# Channel.net
KiCad netlist of a schematic drawn in Altium Designer
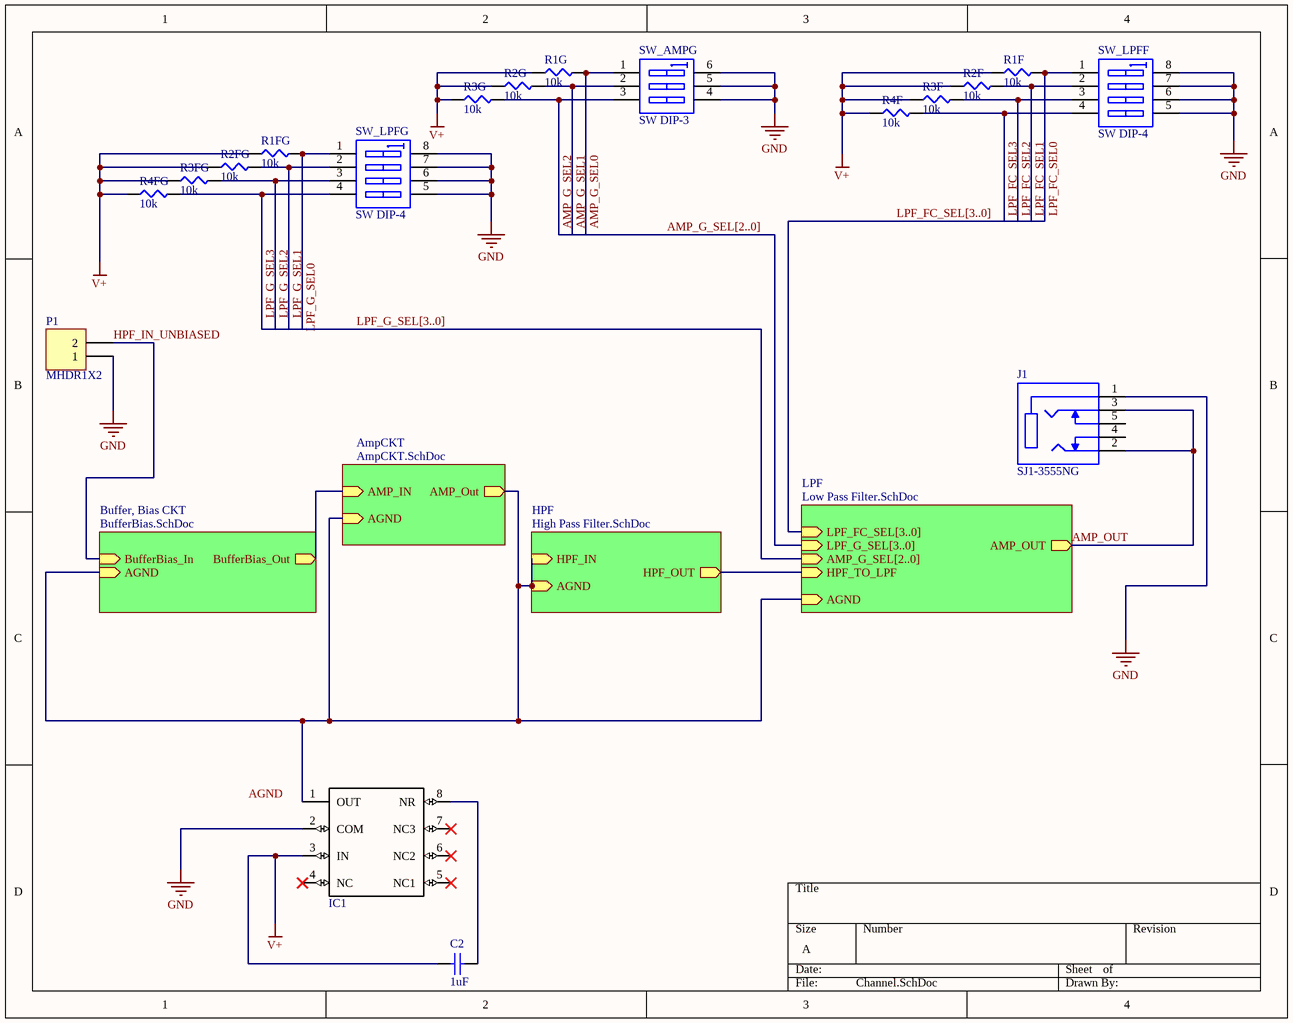
[diagram p0: Channel.SchDoc]

(export (version "E")
  (design (tool "Eeschema 10.0.6"))
  (components
    (comp (ref "C2")
      (value "1uF")
      (footprint "SMD-0805C")
      (description "Unpolarized Capacitor")
      (fields (field (name "Comment") "Cap"))
      (libsource (lib "URC_Lib") (part "Cap"))
    )
    (comp (ref "IC1")
      (value "TLE2426")
      (footprint "SO8_M")
      (fields (field (name "MF") "Texas Instruments"))
      (libsource (lib "TLE2426") (part "TLE2426"))
    )
    (comp (ref "J1")
      (value "SJ1-3555NG")
      (footprint "CUI_SJ1-3555NG")
      (description "3.5 mm, Stereo, Right Angle, Through Hole, Isolated Ground, Kinked Pins, Audio Jack Connector")
      (fields (field (name "MF") "CUI Devices"))
      (libsource (lib "SnapEDAsch") (part "SJ1-3555NG"))
    )
    (comp (ref "P1")
      (value "MHDR1X2")
      (footprint "MHDR1X2")
      (description "Header, 2-Pin")
      (fields (field (name "PUBLISHER") "Altium Limited"))
      (libsource (lib "Miscellaneous Connectors") (part "MHDR1X2"))
    )
    (comp (ref "R1F")
      (value "10k")
      (footprint "SMD-0805-RES")
      (description "RES SMD 10K OHM 1% 1/8W 0805")
      (fields
        (field (name "PART NUMBER") "ERJ-6ENF1002V")
        (field (name "DIGI-KEY PART NUMBER") "P10.0KCCT-ND")
      )
      (libsource (lib "Panasonic_ERJ_0805") (part "ERJ-6ENF1002V"))
    )
    (comp (ref "R1FG")
      (value "10k")
      (footprint "SMD-0805-RES")
      (description "RES SMD 10K OHM 1% 1/8W 0805")
      (fields
        (field (name "PART NUMBER") "ERJ-6ENF1002V")
        (field (name "DIGI-KEY PART NUMBER") "P10.0KCCT-ND")
      )
      (libsource (lib "Panasonic_ERJ_0805") (part "ERJ-6ENF1002V"))
    )
    (comp (ref "R1G")
      (value "10k")
      (footprint "SMD-0805-RES")
      (description "RES SMD 10K OHM 1% 1/8W 0805")
      (fields
        (field (name "PART NUMBER") "ERJ-6ENF1002V")
        (field (name "DIGI-KEY PART NUMBER") "P10.0KCCT-ND")
      )
      (libsource (lib "Panasonic_ERJ_0805") (part "ERJ-6ENF1002V"))
    )
    (comp (ref "R2F")
      (value "10k")
      (footprint "SMD-0805-RES")
      (description "RES SMD 10K OHM 1% 1/8W 0805")
      (fields
        (field (name "PART NUMBER") "ERJ-6ENF1002V")
        (field (name "DIGI-KEY PART NUMBER") "P10.0KCCT-ND")
      )
      (libsource (lib "Panasonic_ERJ_0805") (part "ERJ-6ENF1002V"))
    )
    (comp (ref "R2FG")
      (value "10k")
      (footprint "SMD-0805-RES")
      (description "RES SMD 10K OHM 1% 1/8W 0805")
      (fields
        (field (name "PART NUMBER") "ERJ-6ENF1002V")
        (field (name "DIGI-KEY PART NUMBER") "P10.0KCCT-ND")
      )
      (libsource (lib "Panasonic_ERJ_0805") (part "ERJ-6ENF1002V"))
    )
    (comp (ref "R2G")
      (value "10k")
      (footprint "SMD-0805-RES")
      (description "RES SMD 10K OHM 1% 1/8W 0805")
      (fields
        (field (name "PART NUMBER") "ERJ-6ENF1002V")
        (field (name "DIGI-KEY PART NUMBER") "P10.0KCCT-ND")
      )
      (libsource (lib "Panasonic_ERJ_0805") (part "ERJ-6ENF1002V"))
    )
    (comp (ref "R3F")
      (value "10k")
      (footprint "SMD-0805-RES")
      (description "RES SMD 10K OHM 1% 1/8W 0805")
      (fields
        (field (name "PART NUMBER") "ERJ-6ENF1002V")
        (field (name "DIGI-KEY PART NUMBER") "P10.0KCCT-ND")
      )
      (libsource (lib "Panasonic_ERJ_0805") (part "ERJ-6ENF1002V"))
    )
    (comp (ref "R3FG")
      (value "10k")
      (footprint "SMD-0805-RES")
      (description "RES SMD 10K OHM 1% 1/8W 0805")
      (fields
        (field (name "PART NUMBER") "ERJ-6ENF1002V")
        (field (name "DIGI-KEY PART NUMBER") "P10.0KCCT-ND")
      )
      (libsource (lib "Panasonic_ERJ_0805") (part "ERJ-6ENF1002V"))
    )
    (comp (ref "R3G")
      (value "10k")
      (footprint "SMD-0805-RES")
      (description "RES SMD 10K OHM 1% 1/8W 0805")
      (fields
        (field (name "PART NUMBER") "ERJ-6ENF1002V")
        (field (name "DIGI-KEY PART NUMBER") "P10.0KCCT-ND")
      )
      (libsource (lib "Panasonic_ERJ_0805") (part "ERJ-6ENF1002V"))
    )
    (comp (ref "R4F")
      (value "10k")
      (footprint "SMD-0805-RES")
      (description "RES SMD 10K OHM 1% 1/8W 0805")
      (fields
        (field (name "PART NUMBER") "ERJ-6ENF1002V")
        (field (name "DIGI-KEY PART NUMBER") "P10.0KCCT-ND")
      )
      (libsource (lib "Panasonic_ERJ_0805") (part "ERJ-6ENF1002V"))
    )
    (comp (ref "R4FG")
      (value "10k")
      (footprint "SMD-0805-RES")
      (description "RES SMD 10K OHM 1% 1/8W 0805")
      (fields
        (field (name "PART NUMBER") "ERJ-6ENF1002V")
        (field (name "DIGI-KEY PART NUMBER") "P10.0KCCT-ND")
      )
      (libsource (lib "Panasonic_ERJ_0805") (part "ERJ-6ENF1002V"))
    )
    (comp (ref "SW_AMPG")
      (value "SW DIP-3")
      (footprint "DIP-6")
      (description "DIP Switch, 3 Position, SPST")
      (fields (field (name "PUBLISHER") "Altium Limited"))
      (libsource (lib "Miscellaneous Devices") (part "SW DIP-3"))
    )
    (comp (ref "SW_LPFF")
      (value "SW DIP-4")
      (footprint "SO8_L")
      (description "DIP Switch, 4 Position, SPST")
      (fields (field (name "PUBLISHER") "Altium Limited"))
      (libsource (lib "Miscellaneous Devices") (part "SW DIP-4"))
    )
    (comp (ref "SW_LPFG")
      (value "SW DIP-4")
      (footprint "SO8_L")
      (description "DIP Switch, 4 Position, SPST")
      (fields (field (name "PUBLISHER") "Altium Limited"))
      (libsource (lib "Miscellaneous Devices") (part "SW DIP-4"))
    )
  )
  (nets
    (net (code "1") (name "/AMP_G_SEL0") (class "Default")
      (node (ref "R1G") (pin "2") (pinfunction "2_2") (pintype "passive"))
      (node (ref "SW_AMPG") (pin "1") (pinfunction "A1_1") (pintype "passive"))
    )
    (net (code "2") (name "/AMP_G_SEL1") (class "Default")
      (node (ref "R2G") (pin "2") (pinfunction "2_2") (pintype "passive"))
      (node (ref "SW_AMPG") (pin "2") (pinfunction "A2_2") (pintype "passive"))
    )
    (net (code "3") (name "/AMP_G_SEL2") (class "Default")
      (node (ref "R3G") (pin "2") (pinfunction "2_2") (pintype "passive"))
      (node (ref "SW_AMPG") (pin "3") (pinfunction "A3_3") (pintype "passive"))
    )
    (net (code "5") (name "/AMP_OUT") (class "Default")
      (node (ref "J1") (pin "2") (pinfunction "2_2") (pintype "passive"))
      (node (ref "J1") (pin "3") (pinfunction "3_3") (pintype "passive"))
    )
    (net (code "6") (name "/AMP_Out") (class "Default")
      (node (ref "IC1") (pin "1") (pinfunction "OUT_1") (pintype "power_in"))
    )
    (net (code "8") (name "/HPF_IN_UNBIASED") (class "Default")
      (node (ref "P1") (pin "2") (pinfunction "2_2") (pintype "passive"))
    )
    (net (code "10") (name "/LPF_FC_SEL0") (class "Default")
      (node (ref "R1F") (pin "2") (pinfunction "2_2") (pintype "passive"))
      (node (ref "SW_LPFF") (pin "1") (pinfunction "A1_1") (pintype "passive"))
    )
    (net (code "11") (name "/LPF_FC_SEL1") (class "Default")
      (node (ref "R2F") (pin "2") (pinfunction "2_2") (pintype "passive"))
      (node (ref "SW_LPFF") (pin "2") (pinfunction "A2_2") (pintype "passive"))
    )
    (net (code "12") (name "/LPF_FC_SEL2") (class "Default")
      (node (ref "R3F") (pin "2") (pinfunction "2_2") (pintype "passive"))
      (node (ref "SW_LPFF") (pin "3") (pinfunction "A3_3") (pintype "passive"))
    )
    (net (code "13") (name "/LPF_FC_SEL3") (class "Default")
      (node (ref "R4F") (pin "2") (pinfunction "2_2") (pintype "passive"))
      (node (ref "SW_LPFF") (pin "4") (pinfunction "A4_4") (pintype "passive"))
    )
    (net (code "15") (name "/LPF_G_SEL0") (class "Default")
      (node (ref "R1FG") (pin "2") (pinfunction "2_2") (pintype "passive"))
      (node (ref "SW_LPFG") (pin "1") (pinfunction "A1_1") (pintype "passive"))
    )
    (net (code "16") (name "/LPF_G_SEL1") (class "Default")
      (node (ref "R2FG") (pin "2") (pinfunction "2_2") (pintype "passive"))
      (node (ref "SW_LPFG") (pin "2") (pinfunction "A2_2") (pintype "passive"))
    )
    (net (code "17") (name "/LPF_G_SEL2") (class "Default")
      (node (ref "R3FG") (pin "2") (pinfunction "2_2") (pintype "passive"))
      (node (ref "SW_LPFG") (pin "3") (pinfunction "A3_3") (pintype "passive"))
    )
    (net (code "18") (name "/LPF_G_SEL3") (class "Default")
      (node (ref "R4FG") (pin "2") (pinfunction "2_2") (pintype "passive"))
      (node (ref "SW_LPFG") (pin "4") (pinfunction "A4_4") (pintype "passive"))
    )
    (net (code "20") (name "GND") (class "Default")
      (node (ref "IC1") (pin "2") (pinfunction "COM_2") (pintype "bidirectional"))
      (node (ref "J1") (pin "1") (pinfunction "1_1") (pintype "passive"))
      (node (ref "P1") (pin "1") (pinfunction "1_1") (pintype "passive"))
      (node (ref "SW_AMPG") (pin "4") (pinfunction "B3_4") (pintype "passive"))
      (node (ref "SW_AMPG") (pin "5") (pinfunction "B2_5") (pintype "passive"))
      (node (ref "SW_AMPG") (pin "6") (pinfunction "B1_6") (pintype "passive"))
      (node (ref "SW_LPFF") (pin "5") (pinfunction "B4_5") (pintype "passive"))
      (node (ref "SW_LPFF") (pin "6") (pinfunction "B3_6") (pintype "passive"))
      (node (ref "SW_LPFF") (pin "7") (pinfunction "B2_7") (pintype "passive"))
      (node (ref "SW_LPFF") (pin "8") (pinfunction "B1_8") (pintype "passive"))
      (node (ref "SW_LPFG") (pin "5") (pinfunction "B4_5") (pintype "passive"))
      (node (ref "SW_LPFG") (pin "6") (pinfunction "B3_6") (pintype "passive"))
      (node (ref "SW_LPFG") (pin "7") (pinfunction "B2_7") (pintype "passive"))
      (node (ref "SW_LPFG") (pin "8") (pinfunction "B1_8") (pintype "passive"))
    )
    (net (code "21") (name "Net-(IC1-NR)") (class "Default")
      (node (ref "C2") (pin "1") (pinfunction "1_1") (pintype "passive"))
      (node (ref "IC1") (pin "8") (pinfunction "NR_8") (pintype "bidirectional"))
    )
    (net (code "22") (name "V+") (class "Default")
      (node (ref "C2") (pin "2") (pinfunction "2_2") (pintype "passive"))
      (node (ref "IC1") (pin "3") (pinfunction "IN_3") (pintype "bidirectional"))
      (node (ref "R1F") (pin "1") (pinfunction "1_1") (pintype "passive"))
      (node (ref "R1FG") (pin "1") (pinfunction "1_1") (pintype "passive"))
      (node (ref "R1G") (pin "1") (pinfunction "1_1") (pintype "passive"))
      (node (ref "R2F") (pin "1") (pinfunction "1_1") (pintype "passive"))
      (node (ref "R2FG") (pin "1") (pinfunction "1_1") (pintype "passive"))
      (node (ref "R2G") (pin "1") (pinfunction "1_1") (pintype "passive"))
      (node (ref "R3F") (pin "1") (pinfunction "1_1") (pintype "passive"))
      (node (ref "R3FG") (pin "1") (pinfunction "1_1") (pintype "passive"))
      (node (ref "R3G") (pin "1") (pinfunction "1_1") (pintype "passive"))
      (node (ref "R4F") (pin "1") (pinfunction "1_1") (pintype "passive"))
      (node (ref "R4FG") (pin "1") (pinfunction "1_1") (pintype "passive"))
    )
    (net (code "23") (name "unconnected-(IC1-NC-Pad4)") (class "Default")
      (node (ref "IC1") (pin "4") (pinfunction "NC_4") (pintype "bidirectional+no_connect"))
    )
    (net (code "24") (name "unconnected-(IC1-NC1-Pad5)") (class "Default")
      (node (ref "IC1") (pin "5") (pinfunction "NC1_5") (pintype "bidirectional+no_connect"))
    )
    (net (code "25") (name "unconnected-(IC1-NC2-Pad6)") (class "Default")
      (node (ref "IC1") (pin "6") (pinfunction "NC2_6") (pintype "bidirectional+no_connect"))
    )
    (net (code "26") (name "unconnected-(IC1-NC3-Pad7)") (class "Default")
      (node (ref "IC1") (pin "7") (pinfunction "NC3_7") (pintype "bidirectional+no_connect"))
    )
    (net (code "27") (name "unconnected-(J1-Pad4)") (class "Default")
      (node (ref "J1") (pin "4") (pinfunction "4_4") (pintype "passive"))
    )
    (net (code "28") (name "unconnected-(J1-Pad5)") (class "Default")
      (node (ref "J1") (pin "5") (pinfunction "5_5") (pintype "passive"))
    )
  )
)
